# RGB_Matrix.net
KiCad netlist of a schematic drawn in Altium Designer
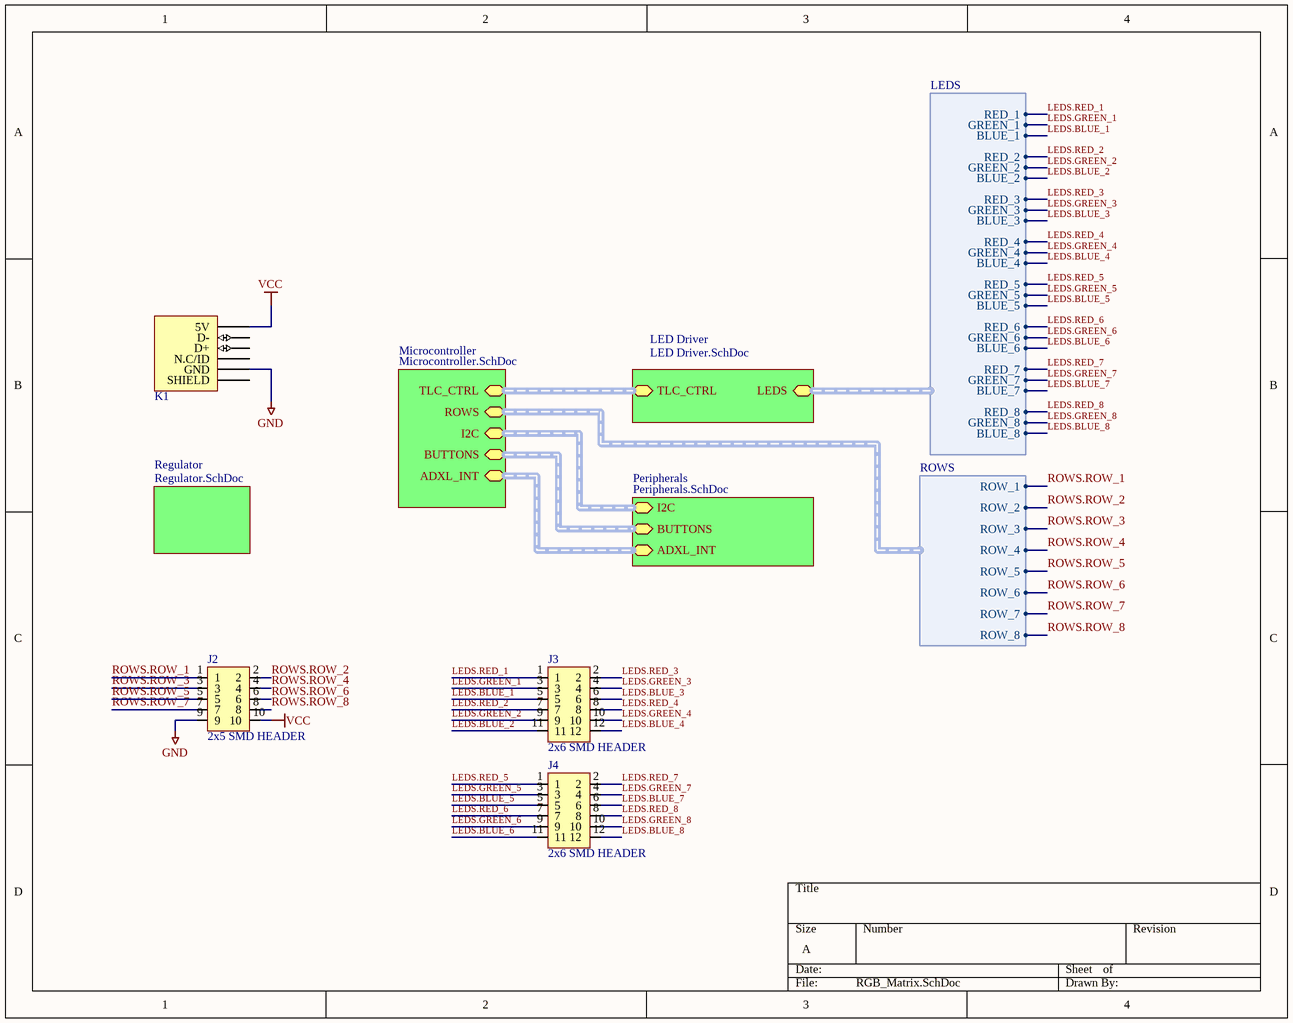
[diagram p0: RGB_Matrix.SchDoc]

(export (version "E")
  (design (tool "Eeschema 10.0.6"))
  (components
    (comp (ref "J2")
      (value "2x5 SMD HEADER")
      (footprint "2x5 SMD HEADER")
      (libsource (lib "Schlib1") (part "2x5 SMD HEADER"))
    )
    (comp (ref "J3")
      (value "2x6 SMD HEADER")
      (footprint "2x6 SMD HEADER")
      (libsource (lib "Schlib1") (part "2x6 SMD HEADER"))
    )
    (comp (ref "J4")
      (value "2x6 SMD HEADER")
      (footprint "2x6 SMD HEADER")
      (libsource (lib "Schlib1") (part "2x6 SMD HEADER"))
    )
    (comp (ref "K1")
      (value "USB_CONNECTOR_5P")
      (footprint "105017-0001")
      (description "Micro USB Type B")
      (libsource (lib "OVLib") (part "USB_CONNECTOR_5P"))
    )
  )
  (nets
    (net (code "6") (name "/LEDS.BLUE_1") (class "Default")
      (node (ref "J3") (pin "5") (pinfunction "5_5") (pintype "passive"))
    )
    (net (code "7") (name "/LEDS.BLUE_2") (class "Default")
      (node (ref "J3") (pin "11") (pinfunction "11_11") (pintype "passive"))
    )
    (net (code "8") (name "/LEDS.BLUE_3") (class "Default")
      (node (ref "J3") (pin "6") (pinfunction "6_6") (pintype "passive"))
    )
    (net (code "9") (name "/LEDS.BLUE_4") (class "Default")
      (node (ref "J3") (pin "12") (pinfunction "12_12") (pintype "passive"))
    )
    (net (code "10") (name "/LEDS.BLUE_5") (class "Default")
      (node (ref "J4") (pin "5") (pinfunction "5_5") (pintype "passive"))
    )
    (net (code "11") (name "/LEDS.BLUE_6") (class "Default")
      (node (ref "J4") (pin "11") (pinfunction "11_11") (pintype "passive"))
    )
    (net (code "12") (name "/LEDS.BLUE_7") (class "Default")
      (node (ref "J4") (pin "6") (pinfunction "6_6") (pintype "passive"))
    )
    (net (code "13") (name "/LEDS.BLUE_8") (class "Default")
      (node (ref "J4") (pin "12") (pinfunction "12_12") (pintype "passive"))
    )
    (net (code "14") (name "/LEDS.GREEN_1") (class "Default")
      (node (ref "J3") (pin "3") (pinfunction "3_3") (pintype "passive"))
    )
    (net (code "15") (name "/LEDS.GREEN_2") (class "Default")
      (node (ref "J3") (pin "9") (pinfunction "9_9") (pintype "passive"))
    )
    (net (code "16") (name "/LEDS.GREEN_3") (class "Default")
      (node (ref "J3") (pin "4") (pinfunction "4_4") (pintype "passive"))
    )
    (net (code "17") (name "/LEDS.GREEN_4") (class "Default")
      (node (ref "J3") (pin "10") (pinfunction "10_10") (pintype "passive"))
    )
    (net (code "18") (name "/LEDS.GREEN_5") (class "Default")
      (node (ref "J4") (pin "3") (pinfunction "3_3") (pintype "passive"))
    )
    (net (code "19") (name "/LEDS.GREEN_6") (class "Default")
      (node (ref "J4") (pin "9") (pinfunction "9_9") (pintype "passive"))
    )
    (net (code "20") (name "/LEDS.GREEN_7") (class "Default")
      (node (ref "J4") (pin "4") (pinfunction "4_4") (pintype "passive"))
    )
    (net (code "21") (name "/LEDS.GREEN_8") (class "Default")
      (node (ref "J4") (pin "10") (pinfunction "10_10") (pintype "passive"))
    )
    (net (code "22") (name "/LEDS.RED_1") (class "Default")
      (node (ref "J3") (pin "1") (pinfunction "1_1") (pintype "passive"))
    )
    (net (code "23") (name "/LEDS.RED_2") (class "Default")
      (node (ref "J3") (pin "7") (pinfunction "7_7") (pintype "passive"))
    )
    (net (code "24") (name "/LEDS.RED_3") (class "Default")
      (node (ref "J3") (pin "2") (pinfunction "2_2") (pintype "passive"))
    )
    (net (code "25") (name "/LEDS.RED_4") (class "Default")
      (node (ref "J3") (pin "8") (pinfunction "8_8") (pintype "passive"))
    )
    (net (code "26") (name "/LEDS.RED_5") (class "Default")
      (node (ref "J4") (pin "1") (pinfunction "1_1") (pintype "passive"))
    )
    (net (code "27") (name "/LEDS.RED_6") (class "Default")
      (node (ref "J4") (pin "7") (pinfunction "7_7") (pintype "passive"))
    )
    (net (code "28") (name "/LEDS.RED_7") (class "Default")
      (node (ref "J4") (pin "2") (pinfunction "2_2") (pintype "passive"))
    )
    (net (code "29") (name "/LEDS.RED_8") (class "Default")
      (node (ref "J4") (pin "8") (pinfunction "8_8") (pintype "passive"))
    )
    (net (code "30") (name "/ROWS.ROW_1") (class "Default")
      (node (ref "J2") (pin "1") (pinfunction "1_1") (pintype "passive"))
    )
    (net (code "31") (name "/ROWS.ROW_2") (class "Default")
      (node (ref "J2") (pin "2") (pinfunction "2_2") (pintype "passive"))
    )
    (net (code "32") (name "/ROWS.ROW_3") (class "Default")
      (node (ref "J2") (pin "3") (pinfunction "3_3") (pintype "passive"))
    )
    (net (code "33") (name "/ROWS.ROW_4") (class "Default")
      (node (ref "J2") (pin "4") (pinfunction "4_4") (pintype "passive"))
    )
    (net (code "34") (name "/ROWS.ROW_5") (class "Default")
      (node (ref "J2") (pin "5") (pinfunction "5_5") (pintype "passive"))
    )
    (net (code "35") (name "/ROWS.ROW_6") (class "Default")
      (node (ref "J2") (pin "6") (pinfunction "6_6") (pintype "passive"))
    )
    (net (code "36") (name "/ROWS.ROW_7") (class "Default")
      (node (ref "J2") (pin "7") (pinfunction "7_7") (pintype "passive"))
    )
    (net (code "37") (name "/ROWS.ROW_8") (class "Default")
      (node (ref "J2") (pin "8") (pinfunction "8_8") (pintype "passive"))
    )
    (net (code "41") (name "GND") (class "Default")
      (node (ref "J2") (pin "9") (pinfunction "9_9") (pintype "passive"))
      (node (ref "K1") (pin "5") (pinfunction "GND_5") (pintype "power_in"))
    )
    (net (code "42") (name "VCC") (class "Default")
      (node (ref "J2") (pin "10") (pinfunction "10_10") (pintype "passive"))
      (node (ref "K1") (pin "1") (pinfunction "5V_1") (pintype "power_in"))
    )
    (net (code "43") (name "unconnected-(K1-D+-Pad3)") (class "Default")
      (node (ref "K1") (pin "3") (pinfunction "D+_3") (pintype "bidirectional"))
    )
    (net (code "44") (name "unconnected-(K1-D--Pad2)") (class "Default")
      (node (ref "K1") (pin "2") (pinfunction "D-_2") (pintype "bidirectional"))
    )
    (net (code "45") (name "unconnected-(K1-N.C{slash}ID-Pad4)") (class "Default")
      (node (ref "K1") (pin "4") (pinfunction "N.C/ID_4") (pintype "passive"))
    )
    (net (code "46") (name "unconnected-(K1-SHIELD-Pad0)") (class "Default")
      (node (ref "K1") (pin "0") (pinfunction "SHIELD_0") (pintype "power_in"))
    )
  )
)
